# Komfortblinker_ATTINY13.net
KiCad netlist of a schematic drawn in EAGLE
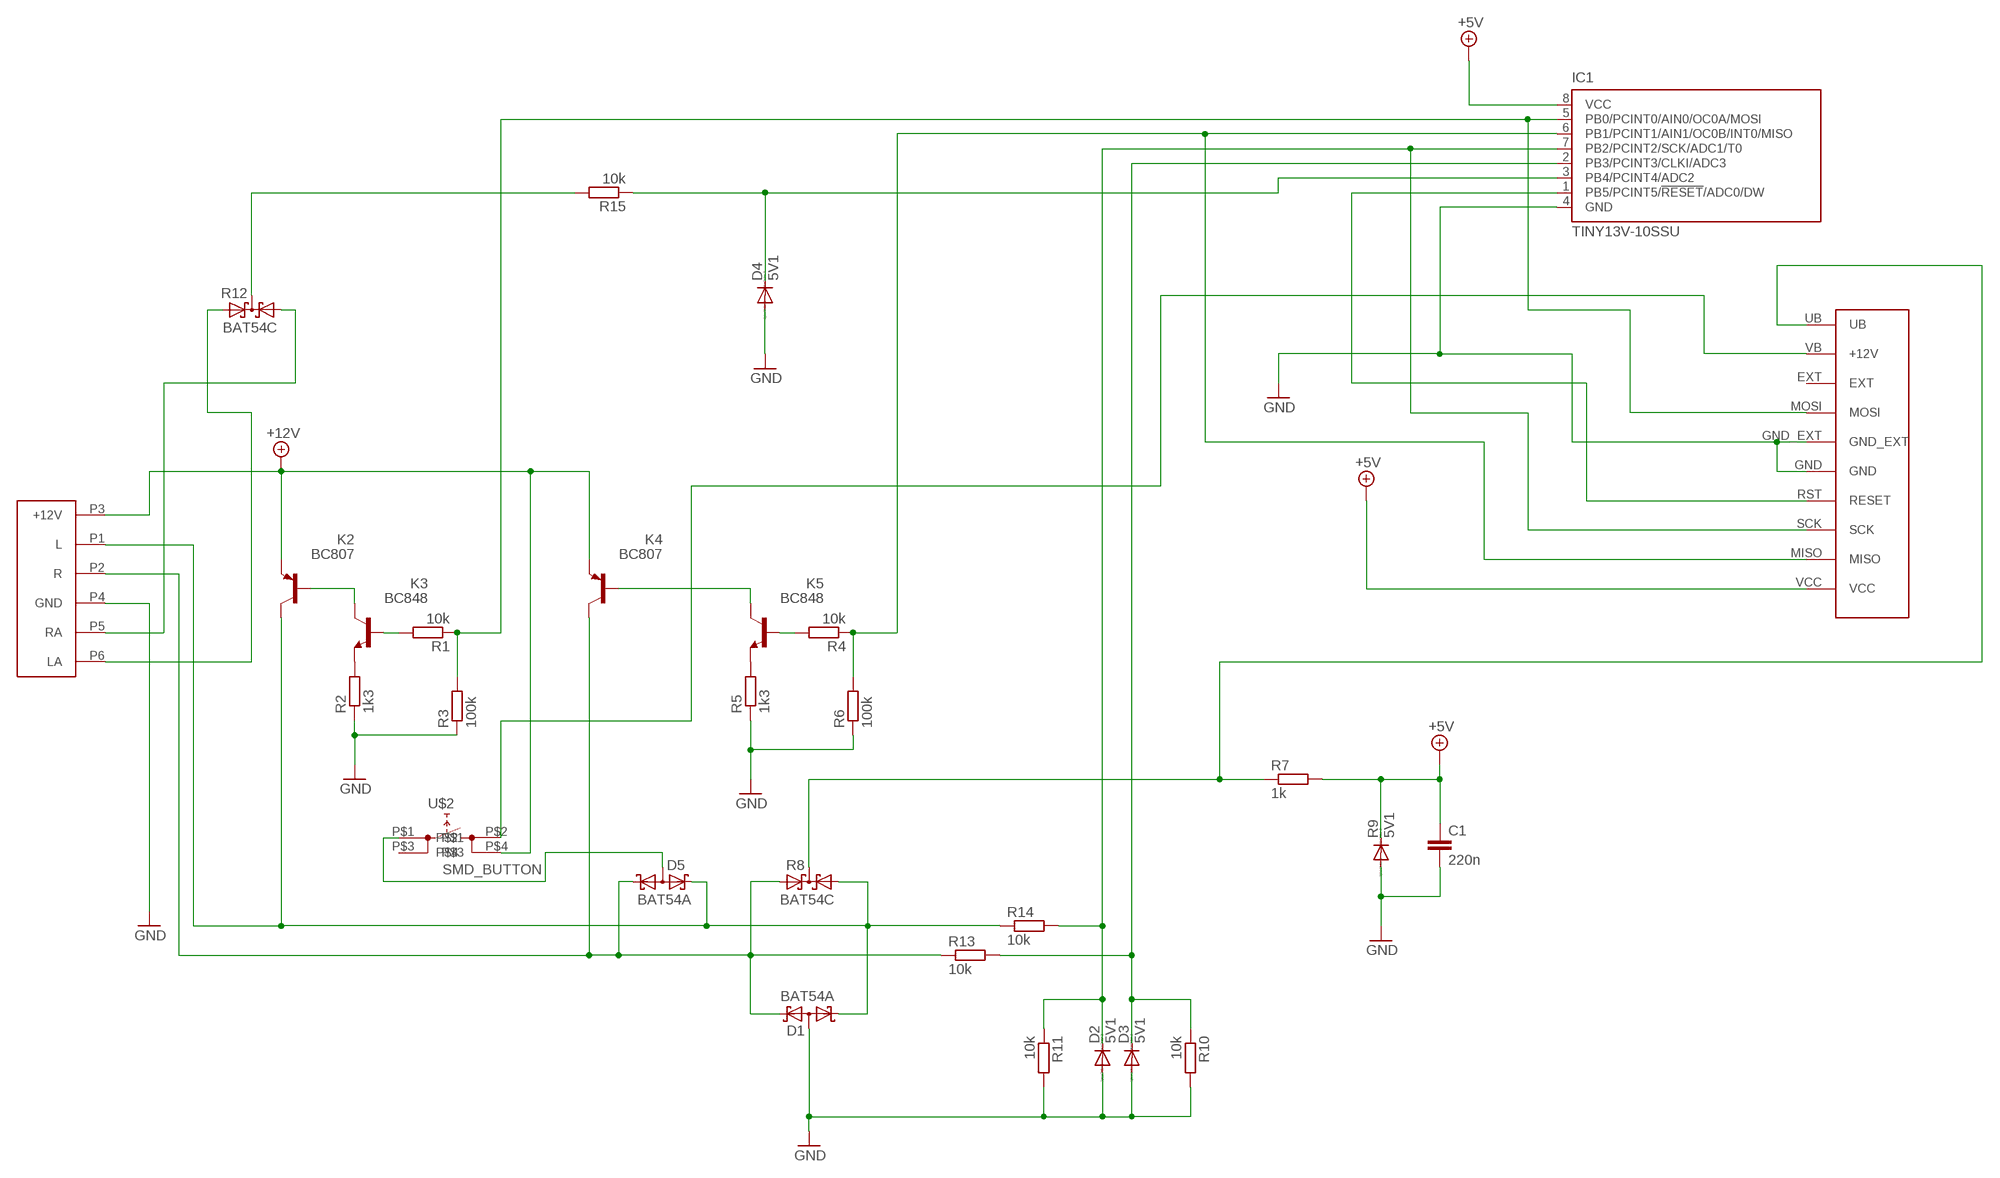
[diagram p0: schematic, sheet 1]

(export (version "E")
  (design (tool "Eeschema 10.0.6"))
  (components
    (comp (ref "C1")
      (value "220n")
      (footprint "eagle-import:C0805")
      (libsource (lib "eagle-import") (part "C-EUC0805"))
    )
    (comp (ref "D1")
      (value "BAT54A")
      (footprint "eagle-import:SOT23")
      (libsource (lib "eagle-import") (part "BAT54A"))
    )
    (comp (ref "D2")
      (value "5V1")
      (footprint "eagle-import:SOD123")
      (libsource (lib "eagle-import") (part "DIODE-SOD123"))
    )
    (comp (ref "D3")
      (value "5V1")
      (footprint "eagle-import:SOD123")
      (libsource (lib "eagle-import") (part "DIODE-SOD123"))
    )
    (comp (ref "D4")
      (value "5V1")
      (footprint "eagle-import:SOD123")
      (libsource (lib "eagle-import") (part "DIODE-SOD123"))
    )
    (comp (ref "D5")
      (value "BAT54A")
      (footprint "eagle-import:SOT23")
      (libsource (lib "eagle-import") (part "BAT54A"))
    )
    (comp (ref "IC1")
      (value "TINY13V-10SSU")
      (footprint "eagle-import:8S1")
      (fields (field (name "MPN") "ATTINY13V-10SSU"))
      (libsource (lib "eagle-import") (part "TINY13SSUV-10"))
    )
    (comp (ref "K2")
      (value "BC807")
      (footprint "eagle-import:SOT23-BEC")
      (libsource (lib "eagle-import") (part "-PNP-SOT23-BECBC858A"))
    )
    (comp (ref "K3")
      (value "BC848")
      (footprint "eagle-import:SOT23")
      (libsource (lib "eagle-import") (part "BC848"))
    )
    (comp (ref "K4")
      (value "BC807")
      (footprint "eagle-import:SOT23-BEC")
      (libsource (lib "eagle-import") (part "-PNP-SOT23-BECBC858A"))
    )
    (comp (ref "K5")
      (value "BC848")
      (footprint "eagle-import:SOT23")
      (libsource (lib "eagle-import") (part "BC848"))
    )
    (comp (ref "R1")
      (value "10k")
      (footprint "eagle-import:R0805")
      (libsource (lib "eagle-import") (part "R-EU_R0805"))
    )
    (comp (ref "R2")
      (value "1k3")
      (footprint "eagle-import:R0805")
      (libsource (lib "eagle-import") (part "R-EU_R0805"))
    )
    (comp (ref "R3")
      (value "100k")
      (footprint "eagle-import:R0805")
      (libsource (lib "eagle-import") (part "R-EU_R0805"))
    )
    (comp (ref "R4")
      (value "10k")
      (footprint "eagle-import:R0805")
      (libsource (lib "eagle-import") (part "R-EU_R0805"))
    )
    (comp (ref "R5")
      (value "1k3")
      (footprint "eagle-import:R0805")
      (libsource (lib "eagle-import") (part "R-EU_R0805"))
    )
    (comp (ref "R6")
      (value "100k")
      (footprint "eagle-import:R0805")
      (libsource (lib "eagle-import") (part "R-EU_R0805"))
    )
    (comp (ref "R7")
      (value "1k")
      (footprint "eagle-import:M0805")
      (libsource (lib "eagle-import") (part "R-EU_M0805"))
    )
    (comp (ref "R8")
      (value "BAT54C")
      (footprint "eagle-import:SOT23")
      (libsource (lib "eagle-import") (part "BAT54C"))
    )
    (comp (ref "R9")
      (value "5V1")
      (footprint "eagle-import:MINIMELF")
      (libsource (lib "eagle-import") (part "DIODE-MINIMELF"))
    )
    (comp (ref "R10")
      (value "10k")
      (footprint "eagle-import:R0805")
      (libsource (lib "eagle-import") (part "R-EU_R0805"))
    )
    (comp (ref "R11")
      (value "10k")
      (footprint "eagle-import:R0805")
      (libsource (lib "eagle-import") (part "R-EU_R0805"))
    )
    (comp (ref "R12")
      (value "BAT54C")
      (footprint "eagle-import:SOT23")
      (libsource (lib "eagle-import") (part "BAT54C"))
    )
    (comp (ref "R13")
      (value "10k")
      (footprint "eagle-import:M0805")
      (libsource (lib "eagle-import") (part "R-EU_M0805"))
    )
    (comp (ref "R14")
      (value "10k")
      (footprint "eagle-import:M0805")
      (libsource (lib "eagle-import") (part "R-EU_M0805"))
    )
    (comp (ref "R15")
      (value "10k")
      (footprint "eagle-import:R0805")
      (libsource (lib "eagle-import") (part "R-EU_R0805"))
    )
    (comp (ref "U$2")
      (value "SMD_BUTTON")
      (footprint "eagle-import:SMD_BUTTON")
      (libsource (lib "eagle-import") (part "SMD_BUTTON"))
    )
    (comp (ref "U$3")
      (value "PROGRAMMING")
      (footprint "eagle-import:PROGRAMMING")
      (libsource (lib "eagle-import") (part "PROGRAMMING"))
    )
    (comp (ref "U$4")
      (value "CON-KOMFORT")
      (footprint "eagle-import:CON-KOMFORT")
      (libsource (lib "eagle-import") (part "CON-KOMFORT"))
    )
  )
  (nets
    (net (code "1") (name "+5V") (class "Default")
      (node (ref "C1") (pin "1") (pinfunction "1_1") (pintype "passive"))
      (node (ref "IC1") (pin "8") (pinfunction "VCC_8") (pintype "power_in"))
      (node (ref "R7") (pin "2") (pinfunction "2_2") (pintype "passive"))
      (node (ref "R9") (pin "C") (pinfunction "C_C") (pintype "passive"))
      (node (ref "U$3") (pin "VCC") (pinfunction "VCC_VCC") (pintype "bidirectional"))
    )
    (net (code "2") (name "+12V") (class "Default")
      (node (ref "K2") (pin "E") (pinfunction "E_E") (pintype "passive"))
      (node (ref "K4") (pin "E") (pinfunction "E_E") (pintype "passive"))
      (node (ref "U$2") (pin "P$4") (pinfunction "P$4_P$4") (pintype "bidirectional"))
      (node (ref "U$4") (pin "P3") (pinfunction "+12V_P3") (pintype "bidirectional"))
    )
    (net (code "3") (name "GND") (class "Default")
      (node (ref "C1") (pin "2") (pinfunction "2_2") (pintype "passive"))
      (node (ref "D1") (pin "3") (pinfunction "AA_3") (pintype "passive"))
      (node (ref "D2") (pin "A") (pinfunction "A_A") (pintype "passive"))
      (node (ref "D3") (pin "A") (pinfunction "A_A") (pintype "passive"))
      (node (ref "D4") (pin "A") (pinfunction "A_A") (pintype "passive"))
      (node (ref "IC1") (pin "4") (pinfunction "GND_4") (pintype "power_in"))
      (node (ref "R10") (pin "2") (pinfunction "2_2") (pintype "passive"))
      (node (ref "R11") (pin "2") (pinfunction "2_2") (pintype "passive"))
      (node (ref "R2") (pin "1") (pinfunction "1_1") (pintype "passive"))
      (node (ref "R3") (pin "1") (pinfunction "1_1") (pintype "passive"))
      (node (ref "R5") (pin "1") (pinfunction "1_1") (pintype "passive"))
      (node (ref "R6") (pin "1") (pinfunction "1_1") (pintype "passive"))
      (node (ref "R9") (pin "A") (pinfunction "A_A") (pintype "passive"))
      (node (ref "U$3") (pin "GND") (pinfunction "GND_GND") (pintype "bidirectional"))
      (node (ref "U$3") (pin "GND_EXT") (pinfunction "GND_EXT_GND_EXT") (pintype "bidirectional"))
      (node (ref "U$4") (pin "P4") (pinfunction "GND_P4") (pintype "bidirectional"))
    )
    (net (code "4") (name "Net-(D1-K1)") (class "Default")
      (node (ref "D1") (pin "1") (pinfunction "K1_1") (pintype "passive"))
      (node (ref "D5") (pin "2") (pinfunction "K2_2") (pintype "passive"))
      (node (ref "K2") (pin "C") (pinfunction "C_C") (pintype "passive"))
      (node (ref "R14") (pin "1") (pinfunction "1_1") (pintype "passive"))
      (node (ref "R8") (pin "1") (pinfunction "A1_1") (pintype "passive"))
      (node (ref "U$4") (pin "P1") (pinfunction "L_P1") (pintype "bidirectional"))
    )
    (net (code "5") (name "Net-(D1-K2)") (class "Default")
      (node (ref "D1") (pin "2") (pinfunction "K2_2") (pintype "passive"))
      (node (ref "D5") (pin "1") (pinfunction "K1_1") (pintype "passive"))
      (node (ref "K4") (pin "C") (pinfunction "C_C") (pintype "passive"))
      (node (ref "R13") (pin "1") (pinfunction "1_1") (pintype "passive"))
      (node (ref "R8") (pin "2") (pinfunction "A2_2") (pintype "passive"))
      (node (ref "U$4") (pin "P2") (pinfunction "R_P2") (pintype "bidirectional"))
    )
    (net (code "6") (name "Net-(D5-AA)") (class "Default")
      (node (ref "D5") (pin "3") (pinfunction "AA_3") (pintype "passive"))
      (node (ref "U$2") (pin "P$1") (pinfunction "P$1_P$1") (pintype "bidirectional"))
    )
    (net (code "7") (name "Net-(IC1-PB0{slash}PCINT0{slash}AIN0{slash}OC0A{slash}MOSI)") (class "Default")
      (node (ref "IC1") (pin "5") (pinfunction "PB0/PCINT0/AIN0/OC0A/MOSI_5") (pintype "bidirectional"))
      (node (ref "R1") (pin "1") (pinfunction "1_1") (pintype "passive"))
      (node (ref "R3") (pin "2") (pinfunction "2_2") (pintype "passive"))
      (node (ref "U$3") (pin "MOSI") (pinfunction "MOSI_MOSI") (pintype "bidirectional"))
    )
    (net (code "8") (name "Net-(IC1-PB1{slash}PCINT1{slash}AIN1{slash}OC0B{slash}INT0{slash}MISO)") (class "Default")
      (node (ref "IC1") (pin "6") (pinfunction "PB1/PCINT1/AIN1/OC0B/INT0/MISO_6") (pintype "bidirectional"))
      (node (ref "R4") (pin "1") (pinfunction "1_1") (pintype "passive"))
      (node (ref "R6") (pin "2") (pinfunction "2_2") (pintype "passive"))
      (node (ref "U$3") (pin "MISO") (pinfunction "MISO_MISO") (pintype "bidirectional"))
    )
    (net (code "9") (name "Net-(IC1-PB2{slash}PCINT2{slash}SCK{slash}ADC1{slash}T0)") (class "Default")
      (node (ref "D2") (pin "C") (pinfunction "C_C") (pintype "passive"))
      (node (ref "IC1") (pin "7") (pinfunction "PB2/PCINT2/SCK/ADC1/T0_7") (pintype "bidirectional"))
      (node (ref "R11") (pin "1") (pinfunction "1_1") (pintype "passive"))
      (node (ref "R14") (pin "2") (pinfunction "2_2") (pintype "passive"))
      (node (ref "U$3") (pin "SCK") (pinfunction "SCK_SCK") (pintype "bidirectional"))
    )
    (net (code "10") (name "Net-(IC1-PB3{slash}PCINT3{slash}CLKI{slash}ADC3)") (class "Default")
      (node (ref "D3") (pin "C") (pinfunction "C_C") (pintype "passive"))
      (node (ref "IC1") (pin "2") (pinfunction "PB3/PCINT3/CLKI/ADC3_2") (pintype "bidirectional"))
      (node (ref "R10") (pin "1") (pinfunction "1_1") (pintype "passive"))
      (node (ref "R13") (pin "2") (pinfunction "2_2") (pintype "passive"))
    )
    (net (code "11") (name "Net-(IC1-PB4{slash}PCINT4{slash}ADC2)") (class "Default")
      (node (ref "D4") (pin "C") (pinfunction "C_C") (pintype "passive"))
      (node (ref "IC1") (pin "3") (pinfunction "PB4/PCINT4/ADC2_3") (pintype "bidirectional"))
      (node (ref "R15") (pin "1") (pinfunction "1_1") (pintype "passive"))
    )
    (net (code "12") (name "Net-(IC1-PB5{slash}PCINT5{slash}~{RESET}{slash}ADC0{slash}DW)") (class "Default")
      (node (ref "IC1") (pin "1") (pinfunction "PB5/PCINT5/~{RESET}/ADC0/DW_1") (pintype "bidirectional"))
      (node (ref "U$3") (pin "RST") (pinfunction "RESET_RST") (pintype "bidirectional"))
    )
    (net (code "13") (name "Net-(K3-B)") (class "Default")
      (node (ref "K3") (pin "1") (pinfunction "B_1") (pintype "passive"))
      (node (ref "R1") (pin "2") (pinfunction "2_2") (pintype "passive"))
    )
    (net (code "14") (name "Net-(K3-C)") (class "Default")
      (node (ref "K2") (pin "B") (pinfunction "B_B") (pintype "passive"))
      (node (ref "K3") (pin "3") (pinfunction "C_3") (pintype "passive"))
    )
    (net (code "15") (name "Net-(K3-E)") (class "Default")
      (node (ref "K3") (pin "2") (pinfunction "E_2") (pintype "passive"))
      (node (ref "R2") (pin "2") (pinfunction "2_2") (pintype "passive"))
    )
    (net (code "16") (name "Net-(K5-B)") (class "Default")
      (node (ref "K5") (pin "1") (pinfunction "B_1") (pintype "passive"))
      (node (ref "R4") (pin "2") (pinfunction "2_2") (pintype "passive"))
    )
    (net (code "17") (name "Net-(K5-C)") (class "Default")
      (node (ref "K4") (pin "B") (pinfunction "B_B") (pintype "passive"))
      (node (ref "K5") (pin "3") (pinfunction "C_3") (pintype "passive"))
    )
    (net (code "18") (name "Net-(K5-E)") (class "Default")
      (node (ref "K5") (pin "2") (pinfunction "E_2") (pintype "passive"))
      (node (ref "R5") (pin "2") (pinfunction "2_2") (pintype "passive"))
    )
    (net (code "19") (name "Net-(R8-CC)") (class "Default")
      (node (ref "R7") (pin "1") (pinfunction "1_1") (pintype "passive"))
      (node (ref "R8") (pin "3") (pinfunction "CC_3") (pintype "passive"))
      (node (ref "U$3") (pin "UB") (pinfunction "UB_UB") (pintype "bidirectional"))
    )
    (net (code "20") (name "Net-(R12-A1)") (class "Default")
      (node (ref "R12") (pin "1") (pinfunction "A1_1") (pintype "passive"))
      (node (ref "U$4") (pin "P5") (pinfunction "RA_P5") (pintype "bidirectional"))
    )
    (net (code "21") (name "Net-(R12-A2)") (class "Default")
      (node (ref "R12") (pin "2") (pinfunction "A2_2") (pintype "passive"))
      (node (ref "U$4") (pin "P6") (pinfunction "LA_P6") (pintype "bidirectional"))
    )
    (net (code "22") (name "Net-(R12-CC)") (class "Default")
      (node (ref "R12") (pin "3") (pinfunction "CC_3") (pintype "passive"))
      (node (ref "R15") (pin "2") (pinfunction "2_2") (pintype "passive"))
    )
    (net (code "23") (name "Net-(U$3-+12V)") (class "Default")
      (node (ref "U$2") (pin "P$2") (pinfunction "P$2_P$2") (pintype "bidirectional"))
      (node (ref "U$3") (pin "VB") (pinfunction "+12V_VB") (pintype "bidirectional"))
    )
    (net (code "24") (name "unconnected-(U$2-PadP$3)") (class "Default")
      (node (ref "U$2") (pin "P$3") (pinfunction "P$3_P$3") (pintype "bidirectional"))
    )
    (net (code "25") (name "unconnected-(U$3-PadEXT)") (class "Default")
      (node (ref "U$3") (pin "EXT") (pinfunction "EXT_EXT") (pintype "bidirectional"))
    )
  )
)
